# DA_uno_shield_2_0.net
KiCad netlist of a schematic drawn in EAGLE
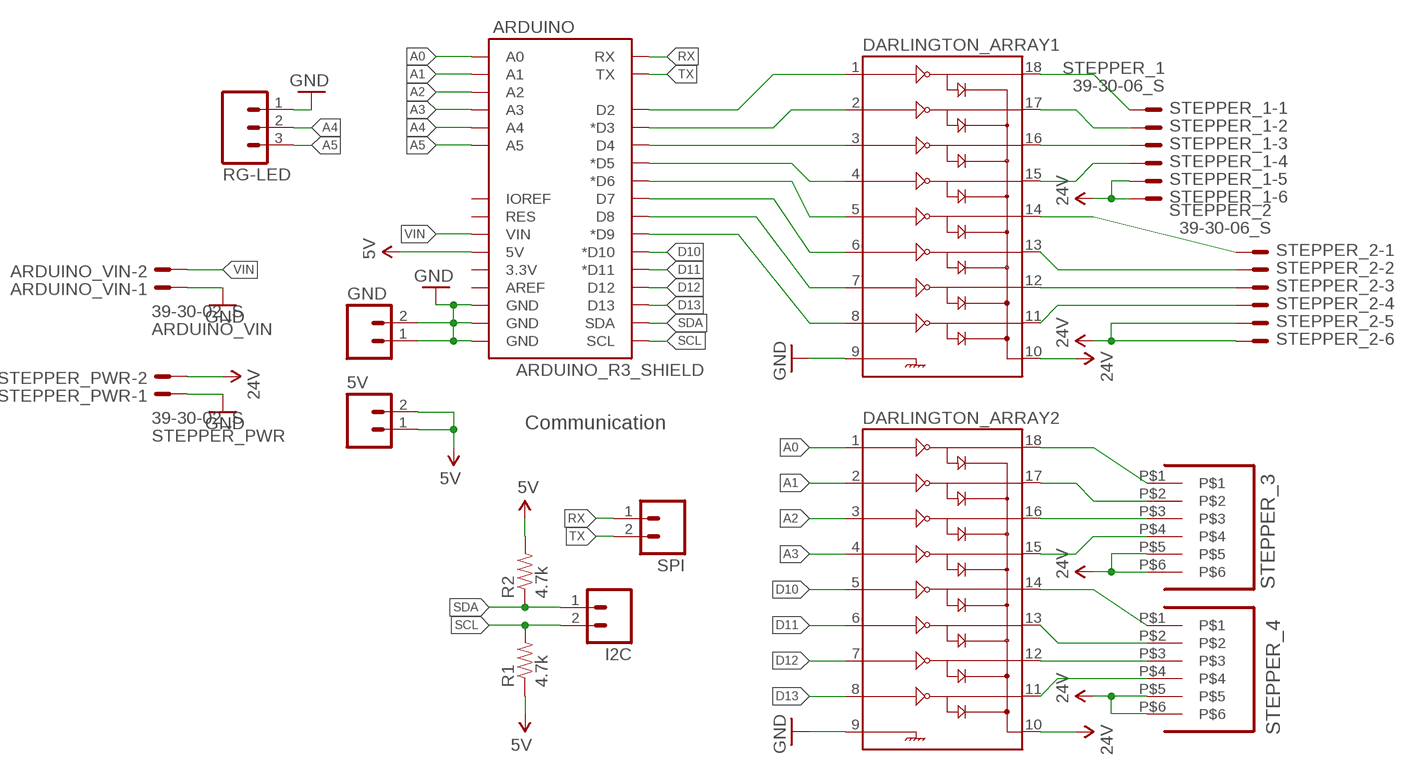
[diagram p0: schematic, sheet 1]

(export (version "E")
  (design (tool "Eeschema 10.0.6"))
  (components
    (comp (ref "5V")
      (value "M021X02_NO_SILK")
      (footprint "eagle-import:1X02_NO_SILK")
      (libsource (lib "eagle-import") (part "M021X02_NO_SILK"))
    )
    (comp (ref "ARDUINO")
      (value "ARDUINO_R3_SHIELD")
      (footprint "eagle-import:UNO_R3_SHIELD")
      (libsource (lib "eagle-import") (part "ARDUINO_R3_SHIELD"))
    )
    (comp (ref "ARDUINO_VIN")
      (value "39-30-02_S")
      (footprint "eagle-import:39-30-_02_")
      (libsource (lib "eagle-import") (part "39-30-?02?_S"))
    )
    (comp (ref "DARLINGTON_ARRAY1")
      (value "ULN2803DIP")
      (footprint "eagle-import:DIL18")
      (libsource (lib "eagle-import") (part "ULN2803DIP"))
    )
    (comp (ref "DARLINGTON_ARRAY2")
      (value "ULN2803DIP")
      (footprint "eagle-import:DIL18")
      (libsource (lib "eagle-import") (part "ULN2803DIP"))
    )
    (comp (ref "GND")
      (value "M021X02_NO_SILK")
      (footprint "eagle-import:1X02_NO_SILK")
      (libsource (lib "eagle-import") (part "M021X02_NO_SILK"))
    )
    (comp (ref "I2C")
      (value "M021X02_NO_SILK")
      (footprint "eagle-import:1X02_NO_SILK")
      (libsource (lib "eagle-import") (part "M021X02_NO_SILK"))
    )
    (comp (ref "R1")
      (value "4.7k")
      (footprint "eagle-import:AXIAL-0.3-KIT")
      (libsource (lib "eagle-import") (part "RESISTORKIT"))
    )
    (comp (ref "R2")
      (value "4.7k")
      (footprint "eagle-import:AXIAL-0.3-KIT")
      (libsource (lib "eagle-import") (part "RESISTORKIT"))
    )
    (comp (ref "RG-LED")
      (value "M03LOCK_NO_SILK")
      (footprint "eagle-import:1X03_LOCK_NO_SILK")
      (libsource (lib "eagle-import") (part "M03LOCK_NO_SILK"))
    )
    (comp (ref "SPI")
      (value "M021X02_NO_SILK")
      (footprint "eagle-import:1X02_NO_SILK")
      (libsource (lib "eagle-import") (part "M021X02_NO_SILK"))
    )
    (comp (ref "STEPPER_1")
      (value "39-30-06_S")
      (footprint "eagle-import:39-30-_06_")
      (libsource (lib "eagle-import") (part "39-30-?06?_S"))
    )
    (comp (ref "STEPPER_2")
      (value "39-30-06_S")
      (footprint "eagle-import:39-30-_06_")
      (libsource (lib "eagle-import") (part "39-30-?06?_S"))
    )
    (comp (ref "STEPPER_3")
      (value "39-29-06")
      (footprint "eagle-import:39-29-_06_")
      (libsource (lib "eagle-import") (part "39-29-?06?"))
    )
    (comp (ref "STEPPER_4")
      (value "39-29-06")
      (footprint "eagle-import:39-29-_06_")
      (libsource (lib "eagle-import") (part "39-29-?06?"))
    )
    (comp (ref "STEPPER_PWR")
      (value "39-30-02_S")
      (footprint "eagle-import:39-30-_02_")
      (libsource (lib "eagle-import") (part "39-30-?02?_S"))
    )
  )
  (nets
    (net (code "1") (name "5V") (class "Default")
      (node (ref "5V") (pin "1") (pinfunction "1_1") (pintype "passive"))
      (node (ref "5V") (pin "2") (pinfunction "2_2") (pintype "passive"))
      (node (ref "ARDUINO") (pin "5V") (pinfunction "5V_5V") (pintype "bidirectional"))
      (node (ref "R1") (pin "P$1") (pinfunction "1_P$1") (pintype "passive"))
      (node (ref "R2") (pin "P$2") (pinfunction "2_P$2") (pintype "passive"))
    )
    (net (code "2") (name "24V") (class "Default")
      (node (ref "DARLINGTON_ARRAY1") (pin "10") (pinfunction "10_10") (pintype "bidirectional"))
      (node (ref "DARLINGTON_ARRAY2") (pin "10") (pinfunction "10_10") (pintype "bidirectional"))
      (node (ref "STEPPER_1") (pin "5") (pinfunction "P_5") (pintype "passive"))
      (node (ref "STEPPER_1") (pin "6") (pinfunction "P_6") (pintype "passive"))
      (node (ref "STEPPER_2") (pin "5") (pinfunction "P_5") (pintype "passive"))
      (node (ref "STEPPER_2") (pin "6") (pinfunction "P_6") (pintype "passive"))
      (node (ref "STEPPER_3") (pin "P$5") (pinfunction "P$5_P$5") (pintype "bidirectional"))
      (node (ref "STEPPER_3") (pin "P$6") (pinfunction "P$6_P$6") (pintype "bidirectional"))
      (node (ref "STEPPER_4") (pin "P$5") (pinfunction "P$5_P$5") (pintype "bidirectional"))
      (node (ref "STEPPER_4") (pin "P$6") (pinfunction "P$6_P$6") (pintype "bidirectional"))
      (node (ref "STEPPER_PWR") (pin "2") (pinfunction "P_2") (pintype "passive"))
    )
    (net (code "3") (name "A0") (class "Default")
      (node (ref "ARDUINO") (pin "A0") (pinfunction "A0_A0") (pintype "bidirectional"))
      (node (ref "DARLINGTON_ARRAY2") (pin "1") (pinfunction "1_1") (pintype "bidirectional"))
    )
    (net (code "4") (name "A1") (class "Default")
      (node (ref "ARDUINO") (pin "A1") (pinfunction "A1_A1") (pintype "bidirectional"))
      (node (ref "DARLINGTON_ARRAY2") (pin "2") (pinfunction "2_2") (pintype "bidirectional"))
    )
    (net (code "5") (name "A2") (class "Default")
      (node (ref "ARDUINO") (pin "A2") (pinfunction "A2_A2") (pintype "bidirectional"))
      (node (ref "DARLINGTON_ARRAY2") (pin "3") (pinfunction "3_3") (pintype "bidirectional"))
    )
    (net (code "6") (name "A3") (class "Default")
      (node (ref "ARDUINO") (pin "A3") (pinfunction "A3_A3") (pintype "bidirectional"))
      (node (ref "DARLINGTON_ARRAY2") (pin "4") (pinfunction "4_4") (pintype "bidirectional"))
    )
    (net (code "7") (name "A4") (class "Default")
      (node (ref "ARDUINO") (pin "A4") (pinfunction "A4_A4") (pintype "bidirectional"))
      (node (ref "RG-LED") (pin "2") (pinfunction "2_2") (pintype "passive"))
    )
    (net (code "8") (name "A5") (class "Default")
      (node (ref "ARDUINO") (pin "A5") (pinfunction "A5_A5") (pintype "bidirectional"))
      (node (ref "RG-LED") (pin "3") (pinfunction "3_3") (pintype "passive"))
    )
    (net (code "9") (name "D10") (class "Default")
      (node (ref "ARDUINO") (pin "D10") (pinfunction "*D10_D10") (pintype "bidirectional"))
      (node (ref "DARLINGTON_ARRAY2") (pin "5") (pinfunction "5_5") (pintype "bidirectional"))
    )
    (net (code "10") (name "D11") (class "Default")
      (node (ref "ARDUINO") (pin "D11") (pinfunction "*D11_D11") (pintype "bidirectional"))
      (node (ref "DARLINGTON_ARRAY2") (pin "6") (pinfunction "6_6") (pintype "bidirectional"))
    )
    (net (code "11") (name "D12") (class "Default")
      (node (ref "ARDUINO") (pin "D12") (pinfunction "D12_D12") (pintype "bidirectional"))
      (node (ref "DARLINGTON_ARRAY2") (pin "7") (pinfunction "7_7") (pintype "bidirectional"))
    )
    (net (code "12") (name "D13") (class "Default")
      (node (ref "ARDUINO") (pin "D13") (pinfunction "D13_D13") (pintype "bidirectional"))
      (node (ref "DARLINGTON_ARRAY2") (pin "8") (pinfunction "8_8") (pintype "bidirectional"))
    )
    (net (code "13") (name "GND") (class "Default")
      (node (ref "ARDUINO") (pin "GND@0") (pinfunction "GND_GND@0") (pintype "bidirectional"))
      (node (ref "ARDUINO") (pin "GND@1") (pinfunction "GND_GND@1") (pintype "bidirectional"))
      (node (ref "ARDUINO") (pin "GND@2") (pinfunction "GND_GND@2") (pintype "bidirectional"))
      (node (ref "ARDUINO_VIN") (pin "1") (pinfunction "P_1") (pintype "passive"))
      (node (ref "DARLINGTON_ARRAY1") (pin "9") (pinfunction "9_9") (pintype "bidirectional"))
      (node (ref "DARLINGTON_ARRAY2") (pin "9") (pinfunction "9_9") (pintype "bidirectional"))
      (node (ref "GND") (pin "1") (pinfunction "1_1") (pintype "passive"))
      (node (ref "GND") (pin "2") (pinfunction "2_2") (pintype "passive"))
      (node (ref "RG-LED") (pin "1") (pinfunction "1_1") (pintype "passive"))
      (node (ref "STEPPER_PWR") (pin "1") (pinfunction "P_1") (pintype "passive"))
    )
    (net (code "14") (name "Net-(ARDUINO-*D3)") (class "Default")
      (node (ref "ARDUINO") (pin "D3") (pinfunction "*D3_D3") (pintype "bidirectional"))
      (node (ref "DARLINGTON_ARRAY1") (pin "2") (pinfunction "2_2") (pintype "bidirectional"))
    )
    (net (code "15") (name "Net-(ARDUINO-*D5)") (class "Default")
      (node (ref "ARDUINO") (pin "D5") (pinfunction "*D5_D5") (pintype "bidirectional"))
      (node (ref "DARLINGTON_ARRAY1") (pin "4") (pinfunction "4_4") (pintype "bidirectional"))
    )
    (net (code "16") (name "Net-(ARDUINO-*D6)") (class "Default")
      (node (ref "ARDUINO") (pin "D6") (pinfunction "*D6_D6") (pintype "bidirectional"))
      (node (ref "DARLINGTON_ARRAY1") (pin "5") (pinfunction "5_5") (pintype "bidirectional"))
    )
    (net (code "17") (name "Net-(ARDUINO-*D9)") (class "Default")
      (node (ref "ARDUINO") (pin "D9") (pinfunction "*D9_D9") (pintype "bidirectional"))
      (node (ref "DARLINGTON_ARRAY1") (pin "8") (pinfunction "8_8") (pintype "bidirectional"))
    )
    (net (code "18") (name "Net-(ARDUINO-PadD2)") (class "Default")
      (node (ref "ARDUINO") (pin "D2") (pinfunction "D2_D2") (pintype "bidirectional"))
      (node (ref "DARLINGTON_ARRAY1") (pin "1") (pinfunction "1_1") (pintype "bidirectional"))
    )
    (net (code "19") (name "Net-(ARDUINO-PadD4)") (class "Default")
      (node (ref "ARDUINO") (pin "D4") (pinfunction "D4_D4") (pintype "bidirectional"))
      (node (ref "DARLINGTON_ARRAY1") (pin "3") (pinfunction "3_3") (pintype "bidirectional"))
    )
    (net (code "20") (name "Net-(ARDUINO-PadD7)") (class "Default")
      (node (ref "ARDUINO") (pin "D7") (pinfunction "D7_D7") (pintype "bidirectional"))
      (node (ref "DARLINGTON_ARRAY1") (pin "6") (pinfunction "6_6") (pintype "bidirectional"))
    )
    (net (code "21") (name "Net-(ARDUINO-PadD8)") (class "Default")
      (node (ref "ARDUINO") (pin "D8") (pinfunction "D8_D8") (pintype "bidirectional"))
      (node (ref "DARLINGTON_ARRAY1") (pin "7") (pinfunction "7_7") (pintype "bidirectional"))
    )
    (net (code "22") (name "Net-(DARLINGTON_ARRAY2-Pad11)") (class "Default")
      (node (ref "DARLINGTON_ARRAY2") (pin "11") (pinfunction "11_11") (pintype "bidirectional"))
      (node (ref "STEPPER_4") (pin "P$4") (pinfunction "P$4_P$4") (pintype "bidirectional"))
    )
    (net (code "23") (name "Net-(DARLINGTON_ARRAY2-Pad12)") (class "Default")
      (node (ref "DARLINGTON_ARRAY2") (pin "12") (pinfunction "12_12") (pintype "bidirectional"))
      (node (ref "STEPPER_4") (pin "P$3") (pinfunction "P$3_P$3") (pintype "bidirectional"))
    )
    (net (code "24") (name "Net-(DARLINGTON_ARRAY2-Pad13)") (class "Default")
      (node (ref "DARLINGTON_ARRAY2") (pin "13") (pinfunction "13_13") (pintype "bidirectional"))
      (node (ref "STEPPER_4") (pin "P$2") (pinfunction "P$2_P$2") (pintype "bidirectional"))
    )
    (net (code "25") (name "Net-(DARLINGTON_ARRAY2-Pad14)") (class "Default")
      (node (ref "DARLINGTON_ARRAY2") (pin "14") (pinfunction "14_14") (pintype "bidirectional"))
      (node (ref "STEPPER_4") (pin "P$1") (pinfunction "P$1_P$1") (pintype "bidirectional"))
    )
    (net (code "26") (name "Net-(DARLINGTON_ARRAY2-Pad15)") (class "Default")
      (node (ref "DARLINGTON_ARRAY2") (pin "15") (pinfunction "15_15") (pintype "bidirectional"))
      (node (ref "STEPPER_3") (pin "P$4") (pinfunction "P$4_P$4") (pintype "bidirectional"))
    )
    (net (code "27") (name "Net-(DARLINGTON_ARRAY2-Pad16)") (class "Default")
      (node (ref "DARLINGTON_ARRAY2") (pin "16") (pinfunction "16_16") (pintype "bidirectional"))
      (node (ref "STEPPER_3") (pin "P$3") (pinfunction "P$3_P$3") (pintype "bidirectional"))
    )
    (net (code "28") (name "Net-(DARLINGTON_ARRAY2-Pad17)") (class "Default")
      (node (ref "DARLINGTON_ARRAY2") (pin "17") (pinfunction "17_17") (pintype "bidirectional"))
      (node (ref "STEPPER_3") (pin "P$2") (pinfunction "P$2_P$2") (pintype "bidirectional"))
    )
    (net (code "29") (name "Net-(DARLINGTON_ARRAY2-Pad18)") (class "Default")
      (node (ref "DARLINGTON_ARRAY2") (pin "18") (pinfunction "18_18") (pintype "bidirectional"))
      (node (ref "STEPPER_3") (pin "P$1") (pinfunction "P$1_P$1") (pintype "bidirectional"))
    )
    (net (code "30") (name "Net-(STEPPER_1A-P)") (class "Default")
      (node (ref "DARLINGTON_ARRAY1") (pin "18") (pinfunction "18_18") (pintype "bidirectional"))
      (node (ref "STEPPER_1") (pin "1") (pinfunction "P_1") (pintype "passive"))
    )
    (net (code "31") (name "Net-(STEPPER_1B-P)") (class "Default")
      (node (ref "DARLINGTON_ARRAY1") (pin "17") (pinfunction "17_17") (pintype "bidirectional"))
      (node (ref "STEPPER_1") (pin "2") (pinfunction "P_2") (pintype "passive"))
    )
    (net (code "32") (name "Net-(STEPPER_1C-P)") (class "Default")
      (node (ref "DARLINGTON_ARRAY1") (pin "16") (pinfunction "16_16") (pintype "bidirectional"))
      (node (ref "STEPPER_1") (pin "3") (pinfunction "P_3") (pintype "passive"))
    )
    (net (code "33") (name "Net-(STEPPER_1D-P)") (class "Default")
      (node (ref "DARLINGTON_ARRAY1") (pin "15") (pinfunction "15_15") (pintype "bidirectional"))
      (node (ref "STEPPER_1") (pin "4") (pinfunction "P_4") (pintype "passive"))
    )
    (net (code "34") (name "Net-(STEPPER_2A-P)") (class "Default")
      (node (ref "DARLINGTON_ARRAY1") (pin "14") (pinfunction "14_14") (pintype "bidirectional"))
      (node (ref "STEPPER_2") (pin "1") (pinfunction "P_1") (pintype "passive"))
    )
    (net (code "35") (name "Net-(STEPPER_2B-P)") (class "Default")
      (node (ref "DARLINGTON_ARRAY1") (pin "13") (pinfunction "13_13") (pintype "bidirectional"))
      (node (ref "STEPPER_2") (pin "2") (pinfunction "P_2") (pintype "passive"))
    )
    (net (code "36") (name "Net-(STEPPER_2C-P)") (class "Default")
      (node (ref "DARLINGTON_ARRAY1") (pin "12") (pinfunction "12_12") (pintype "bidirectional"))
      (node (ref "STEPPER_2") (pin "3") (pinfunction "P_3") (pintype "passive"))
    )
    (net (code "37") (name "Net-(STEPPER_2D-P)") (class "Default")
      (node (ref "DARLINGTON_ARRAY1") (pin "11") (pinfunction "11_11") (pintype "bidirectional"))
      (node (ref "STEPPER_2") (pin "4") (pinfunction "P_4") (pintype "passive"))
    )
    (net (code "38") (name "RX") (class "Default")
      (node (ref "ARDUINO") (pin "RX") (pinfunction "RX_RX") (pintype "bidirectional"))
      (node (ref "SPI") (pin "1") (pinfunction "1_1") (pintype "passive"))
    )
    (net (code "39") (name "SCL") (class "Default")
      (node (ref "ARDUINO") (pin "SCL") (pinfunction "SCL_SCL") (pintype "bidirectional"))
      (node (ref "I2C") (pin "2") (pinfunction "2_2") (pintype "passive"))
      (node (ref "R1") (pin "P$2") (pinfunction "2_P$2") (pintype "passive"))
    )
    (net (code "40") (name "SDA") (class "Default")
      (node (ref "ARDUINO") (pin "SDA") (pinfunction "SDA_SDA") (pintype "bidirectional"))
      (node (ref "I2C") (pin "1") (pinfunction "1_1") (pintype "passive"))
      (node (ref "R2") (pin "P$1") (pinfunction "1_P$1") (pintype "passive"))
    )
    (net (code "41") (name "TX") (class "Default")
      (node (ref "ARDUINO") (pin "TX") (pinfunction "TX_TX") (pintype "bidirectional"))
      (node (ref "SPI") (pin "2") (pinfunction "2_2") (pintype "passive"))
    )
    (net (code "42") (name "VIN") (class "Default")
      (node (ref "ARDUINO") (pin "VIN") (pinfunction "VIN_VIN") (pintype "bidirectional"))
      (node (ref "ARDUINO_VIN") (pin "2") (pinfunction "P_2") (pintype "passive"))
    )
    (net (code "43") (name "unconnected-(ARDUINO-Pad3.3V)") (class "Default")
      (node (ref "ARDUINO") (pin "3.3V") (pinfunction "3.3V_3.3V") (pintype "bidirectional"))
    )
    (net (code "44") (name "unconnected-(ARDUINO-PadAREF)") (class "Default")
      (node (ref "ARDUINO") (pin "AREF") (pinfunction "AREF_AREF") (pintype "bidirectional"))
    )
    (net (code "45") (name "unconnected-(ARDUINO-PadIOREF)") (class "Default")
      (node (ref "ARDUINO") (pin "IOREF") (pinfunction "IOREF_IOREF") (pintype "bidirectional"))
    )
    (net (code "46") (name "unconnected-(ARDUINO-PadRES)") (class "Default")
      (node (ref "ARDUINO") (pin "RES") (pinfunction "RES_RES") (pintype "bidirectional"))
    )
  )
)
